# BlinkyBoard_wide.net
KiCad netlist of a schematic drawn in EAGLE
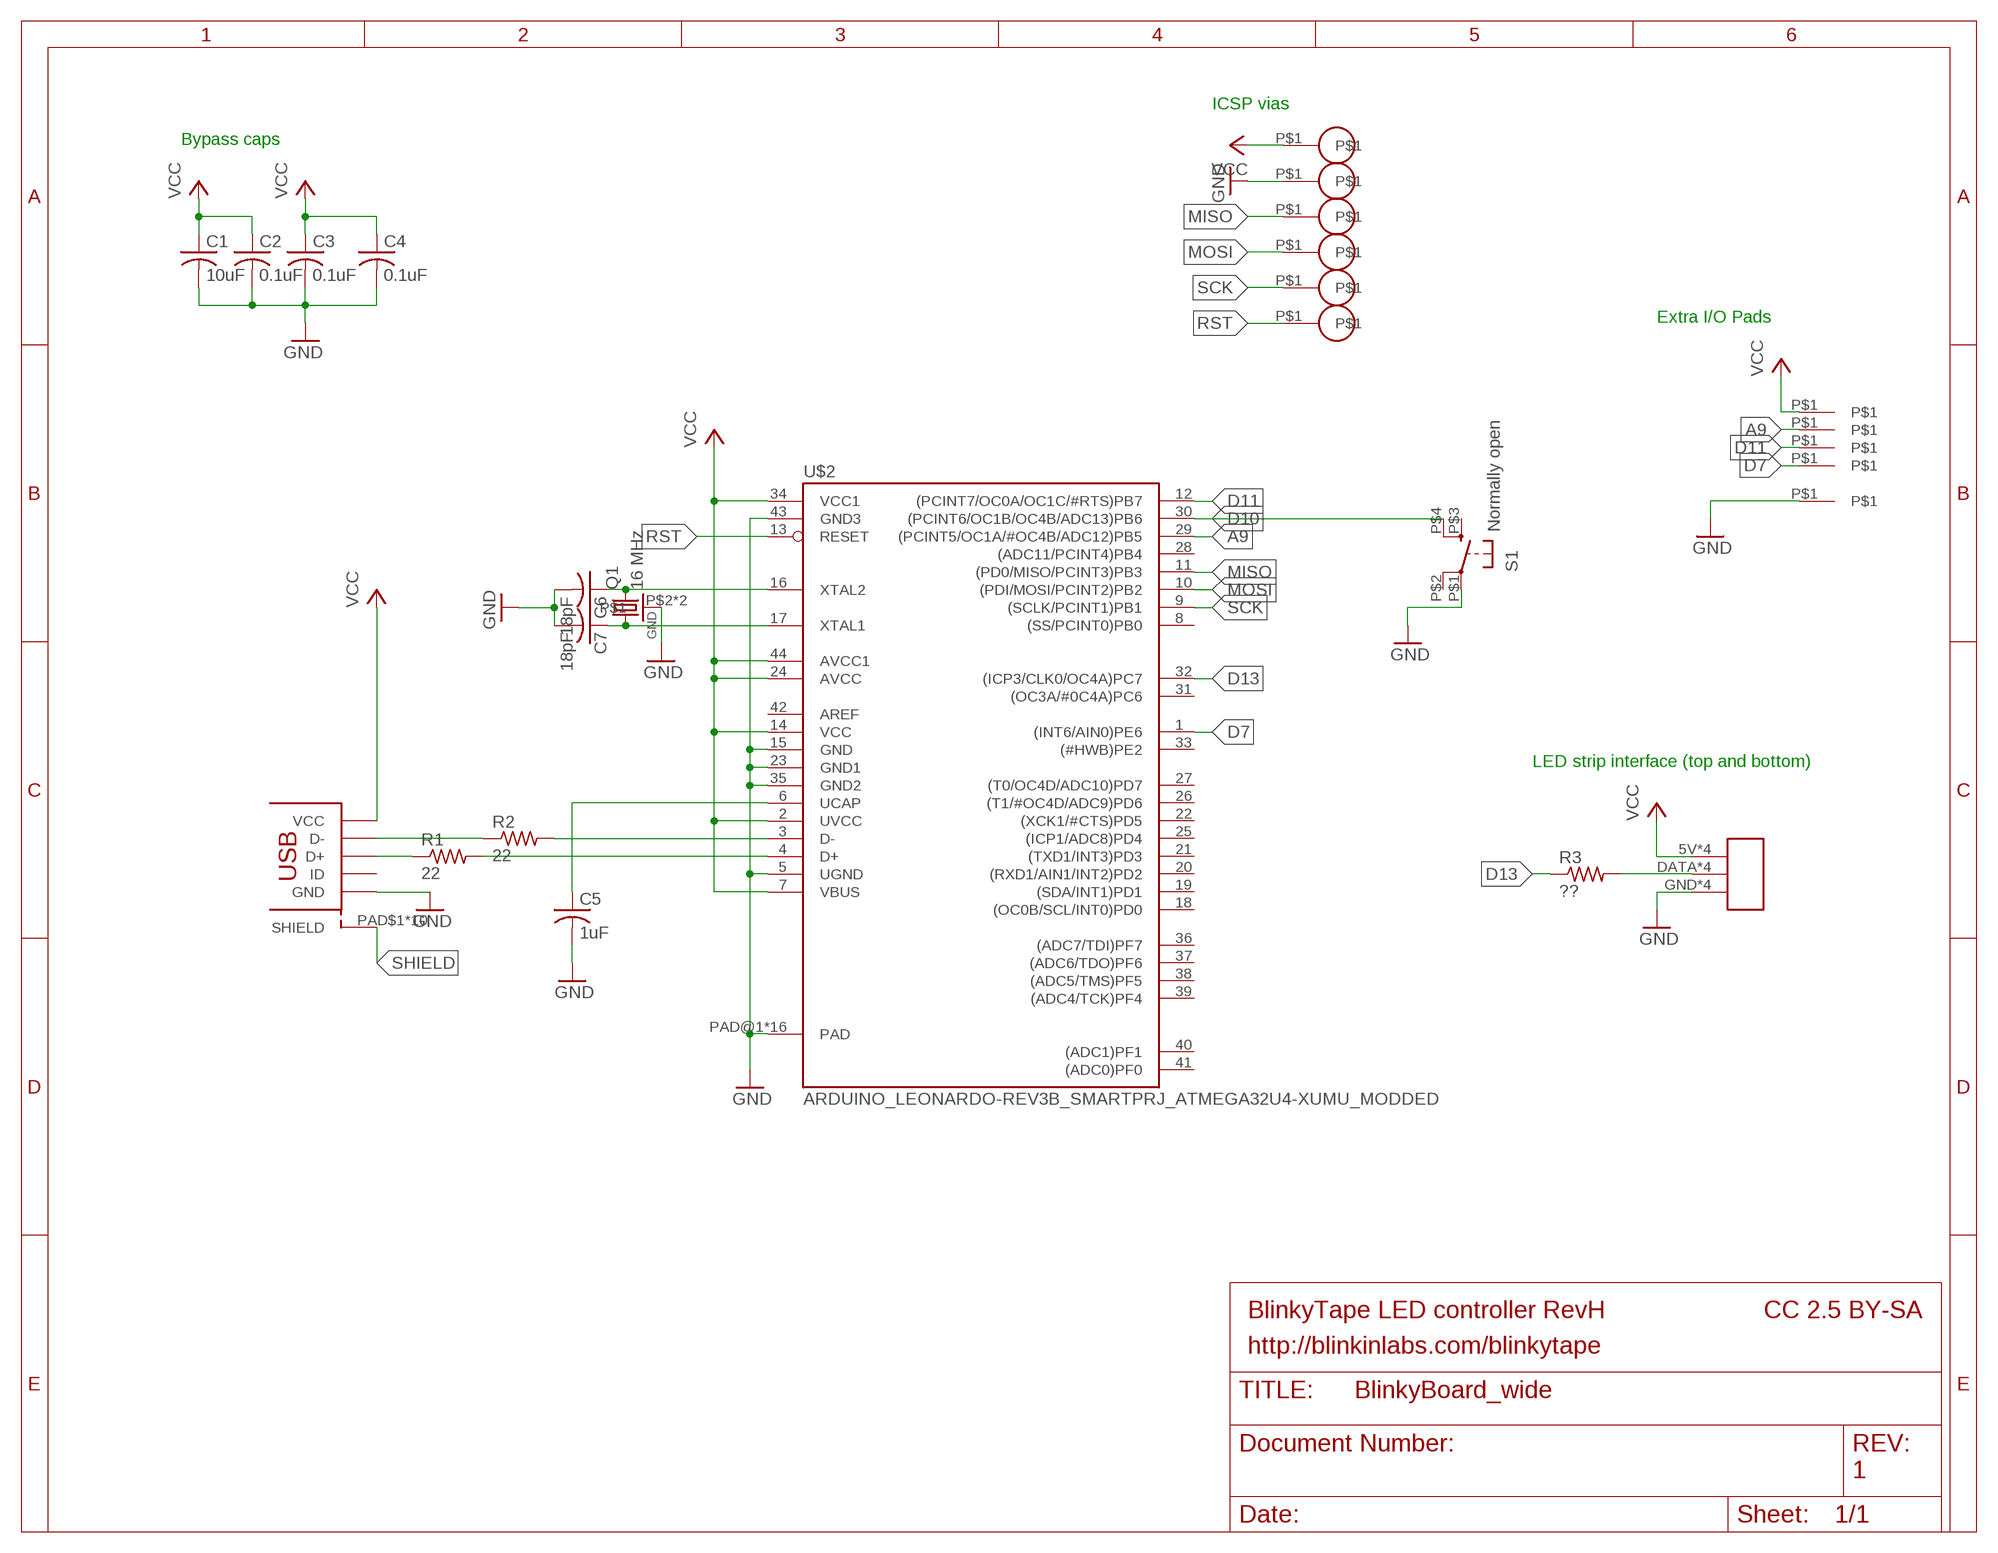
[diagram p0: schematic, sheet 1]

(export (version "E")
  (design (tool "Eeschema 10.0.6"))
  (components
    (comp (ref "C1")
      (value "10uF")
      (footprint "eagle-import:C0603K")
      (libsource (lib "eagle-import") (part "C-USC0603K"))
    )
    (comp (ref "C2")
      (value "0.1uF")
      (footprint "eagle-import:CAP_0402_KEMET_MEDIAN")
      (libsource (lib "eagle-import") (part "C_US"))
    )
    (comp (ref "C3")
      (value "0.1uF")
      (footprint "eagle-import:CAP_0402_KEMET_MEDIAN")
      (libsource (lib "eagle-import") (part "C_US"))
    )
    (comp (ref "C4")
      (value "0.1uF")
      (footprint "eagle-import:CAP_0402_KEMET_MEDIAN")
      (libsource (lib "eagle-import") (part "C_US"))
    )
    (comp (ref "C5")
      (value "1uF")
      (footprint "eagle-import:CAP_0402_KEMET_MEDIAN")
      (libsource (lib "eagle-import") (part "C_US"))
    )
    (comp (ref "C6")
      (value "18pF")
      (footprint "eagle-import:CAP_0402_KEMET_MEDIAN")
      (libsource (lib "eagle-import") (part "C_US"))
    )
    (comp (ref "C7")
      (value "18pF")
      (footprint "eagle-import:CAP_0402_KEMET_MEDIAN")
      (libsource (lib "eagle-import") (part "C_US"))
    )
    (comp (ref "Q1")
      (value "16 MHz")
      (footprint "eagle-import:CRSYTAL_2520")
      (libsource (lib "eagle-import") (part "CRYSTAL_4PAD2520"))
    )
    (comp (ref "R1")
      (value "22")
      (footprint "eagle-import:RES_0402_KEMET_MEDIAN")
      (libsource (lib "eagle-import") (part "R_US"))
    )
    (comp (ref "R2")
      (value "22")
      (footprint "eagle-import:RES_0402_KEMET_MEDIAN")
      (libsource (lib "eagle-import") (part "R_US"))
    )
    (comp (ref "R3")
      (value "??")
      (footprint "eagle-import:RES_0402_KEMET_MEDIAN")
      (libsource (lib "eagle-import") (part "R_US"))
    )
    (comp (ref "S1")
      (value "Normally open")
      (footprint "eagle-import:GLOWBOARD_KMR211G_SWITCH")
      (libsource (lib "eagle-import") (part "GLOWBOARD_KMR211G"))
    )
    (comp (ref "U$1")
      (value "TEST_VIA")
      (footprint "eagle-import:TEST_VIA_.5MM")
      (libsource (lib "eagle-import") (part "TEST_VIA"))
    )
    (comp (ref "U$2")
      (value "ARDUINO_LEONARDO-REV3B_SMARTPRJ_ATMEGA32U4-XUMU_MODDED")
      (footprint "eagle-import:QFN44ML_7X7_LONGLEADS_MOD")
      (libsource (lib "eagle-import") (part "ARDUINO_LEONARDO-REV3B_SMARTPRJ_ATMEGA32U4-XUMU_MODDED"))
    )
    (comp (ref "U$3")
      (value "TEST_VIA")
      (footprint "eagle-import:TEST_VIA_.5MM")
      (libsource (lib "eagle-import") (part "TEST_VIA"))
    )
    (comp (ref "U$4")
      (value "MICRO_USBSMT+THRUHULE")
      (footprint "eagle-import:MICRO_USB_FCI_THRUHOLE")
      (libsource (lib "eagle-import") (part "MICRO_USBSMT+THRUHULE"))
    )
    (comp (ref "U$5")
      (value "TEST_VIA")
      (footprint "eagle-import:TEST_VIA_.5MM")
      (libsource (lib "eagle-import") (part "TEST_VIA"))
    )
    (comp (ref "U$6")
      (value "TEST_VIA")
      (footprint "eagle-import:TEST_VIA_.5MM")
      (libsource (lib "eagle-import") (part "TEST_VIA"))
    )
    (comp (ref "U$7")
      (value "TEST_VIA")
      (footprint "eagle-import:TEST_VIA_.5MM")
      (libsource (lib "eagle-import") (part "TEST_VIA"))
    )
    (comp (ref "U$8")
      (value "TEST_VIA")
      (footprint "eagle-import:TEST_VIA_.5MM")
      (libsource (lib "eagle-import") (part "TEST_VIA"))
    )
    (comp (ref "U$9")
      (value "WS2812B_CONNECTORWIDE")
      (footprint "eagle-import:WS2812B_WIDE_CONNECTOR")
      (libsource (lib "eagle-import") (part "WS2812B_CONNECTORWIDE"))
    )
    (comp (ref "U$10")
      (value "TEST_PAD_SMT")
      (footprint "eagle-import:TEST_PAD_SMT")
      (libsource (lib "eagle-import") (part "TEST_PAD_SMT"))
    )
    (comp (ref "U$11")
      (value "TEST_PAD_SMT")
      (footprint "eagle-import:TEST_PAD_SMT")
      (libsource (lib "eagle-import") (part "TEST_PAD_SMT"))
    )
    (comp (ref "U$12")
      (value "TEST_PAD_SMT")
      (footprint "eagle-import:TEST_PAD_SMT")
      (libsource (lib "eagle-import") (part "TEST_PAD_SMT"))
    )
    (comp (ref "U$13")
      (value "TEST_PAD_SMT")
      (footprint "eagle-import:TEST_PAD_SMT")
      (libsource (lib "eagle-import") (part "TEST_PAD_SMT"))
    )
    (comp (ref "U$14")
      (value "TEST_PAD_SMT")
      (footprint "eagle-import:TEST_PAD_SMT")
      (libsource (lib "eagle-import") (part "TEST_PAD_SMT"))
    )
  )
  (nets
    (net (code "1") (name "/AREF") (class "Default")
      (node (ref "U$2") (pin "42") (pinfunction "AREF_42") (pintype "power_in"))
    )
    (net (code "2") (name "A9") (class "Default")
      (node (ref "U$11") (pin "P$1") (pinfunction "P$1_P$1") (pintype "bidirectional"))
      (node (ref "U$2") (pin "29") (pinfunction "(PCINT5/OC1A/#OC4B/ADC12)PB5_29") (pintype "bidirectional"))
    )
    (net (code "3") (name "D7") (class "Default")
      (node (ref "U$10") (pin "P$1") (pinfunction "P$1_P$1") (pintype "bidirectional"))
      (node (ref "U$2") (pin "1") (pinfunction "(INT6/AIN0)PE6_1") (pintype "bidirectional"))
    )
    (net (code "4") (name "D10") (class "Default")
      (node (ref "S1") (pin "P$4") (pinfunction "S1_P$4") (pintype "passive"))
      (node (ref "U$2") (pin "30") (pinfunction "(PCINT6/OC1B/OC4B/ADC13)PB6_30") (pintype "bidirectional"))
    )
    (net (code "5") (name "D11") (class "Default")
      (node (ref "U$14") (pin "P$1") (pinfunction "P$1_P$1") (pintype "bidirectional"))
      (node (ref "U$2") (pin "12") (pinfunction "(PCINT7/OC0A/OC1C/#RTS)PB7_12") (pintype "bidirectional"))
    )
    (net (code "6") (name "D13") (class "Default")
      (node (ref "R3") (pin "P$1") (pinfunction "1_P$1") (pintype "passive"))
      (node (ref "U$2") (pin "32") (pinfunction "(ICP3/CLK0/OC4A)PC7_32") (pintype "bidirectional"))
    )
    (net (code "7") (name "GND") (class "Default")
      (node (ref "C1") (pin "2") (pinfunction "2_2") (pintype "passive"))
      (node (ref "C2") (pin "P$2") (pinfunction "2_P$2") (pintype "passive"))
      (node (ref "C3") (pin "P$2") (pinfunction "2_P$2") (pintype "passive"))
      (node (ref "C4") (pin "P$2") (pinfunction "2_P$2") (pintype "passive"))
      (node (ref "C5") (pin "P$2") (pinfunction "2_P$2") (pintype "passive"))
      (node (ref "C6") (pin "P$2") (pinfunction "2_P$2") (pintype "passive"))
      (node (ref "C7") (pin "P$2") (pinfunction "2_P$2") (pintype "passive"))
      (node (ref "Q1") (pin "P$2") (pinfunction "P$1_P$2") (pintype "bidirectional"))
      (node (ref "Q1") (pin "P$4") (pinfunction "P$1_P$4") (pintype "bidirectional"))
      (node (ref "S1") (pin "P$1") (pinfunction "P_P$1") (pintype "passive"))
      (node (ref "U$13") (pin "P$1") (pinfunction "P$1_P$1") (pintype "bidirectional"))
      (node (ref "U$2") (pin "15") (pinfunction "GND_15") (pintype "power_in"))
      (node (ref "U$2") (pin "23") (pinfunction "GND1_23") (pintype "power_in"))
      (node (ref "U$2") (pin "35") (pinfunction "GND2_35") (pintype "power_in"))
      (node (ref "U$2") (pin "43") (pinfunction "GND3_43") (pintype "power_in"))
      (node (ref "U$2") (pin "5") (pinfunction "UGND_5") (pintype "power_in"))
      (node (ref "U$2") (pin "PAD@1") (pinfunction "PAD_PAD@1") (pintype "power_in"))
      (node (ref "U$2") (pin "PAD@10") (pinfunction "PAD_PAD@10") (pintype "power_in"))
      (node (ref "U$2") (pin "PAD@11") (pinfunction "PAD_PAD@11") (pintype "power_in"))
      (node (ref "U$2") (pin "PAD@12") (pinfunction "PAD_PAD@12") (pintype "power_in"))
      (node (ref "U$2") (pin "PAD@13") (pinfunction "PAD_PAD@13") (pintype "power_in"))
      (node (ref "U$2") (pin "PAD@14") (pinfunction "PAD_PAD@14") (pintype "power_in"))
      (node (ref "U$2") (pin "PAD@15") (pinfunction "PAD_PAD@15") (pintype "power_in"))
      (node (ref "U$2") (pin "PAD@16") (pinfunction "PAD_PAD@16") (pintype "power_in"))
      (node (ref "U$2") (pin "PAD@2") (pinfunction "PAD_PAD@2") (pintype "power_in"))
      (node (ref "U$2") (pin "PAD@3") (pinfunction "PAD_PAD@3") (pintype "power_in"))
      (node (ref "U$2") (pin "PAD@4") (pinfunction "PAD_PAD@4") (pintype "power_in"))
      (node (ref "U$2") (pin "PAD@5") (pinfunction "PAD_PAD@5") (pintype "power_in"))
      (node (ref "U$2") (pin "PAD@6") (pinfunction "PAD_PAD@6") (pintype "power_in"))
      (node (ref "U$2") (pin "PAD@7") (pinfunction "PAD_PAD@7") (pintype "power_in"))
      (node (ref "U$2") (pin "PAD@8") (pinfunction "PAD_PAD@8") (pintype "power_in"))
      (node (ref "U$2") (pin "PAD@9") (pinfunction "PAD_PAD@9") (pintype "power_in"))
      (node (ref "U$4") (pin "PIN$5") (pinfunction "GND_PIN$5") (pintype "bidirectional"))
      (node (ref "U$7") (pin "P$1") (pinfunction "P$1_P$1") (pintype "bidirectional"))
      (node (ref "U$9") (pin "GND") (pinfunction "GND_GND") (pintype "bidirectional"))
      (node (ref "U$9") (pin "GND1") (pinfunction "GND_GND1") (pintype "bidirectional"))
      (node (ref "U$9") (pin "GND_1") (pinfunction "GND_GND_1") (pintype "bidirectional"))
      (node (ref "U$9") (pin "GND_2") (pinfunction "GND_GND_2") (pintype "bidirectional"))
    )
    (net (code "8") (name "MISO") (class "Default")
      (node (ref "U$1") (pin "P$1") (pinfunction "P$1_P$1") (pintype "bidirectional"))
      (node (ref "U$2") (pin "11") (pinfunction "(PD0/MISO/PCINT3)PB3_11") (pintype "bidirectional"))
    )
    (net (code "9") (name "MOSI") (class "Default")
      (node (ref "U$2") (pin "10") (pinfunction "(PDI/MOSI/PCINT2)PB2_10") (pintype "bidirectional"))
      (node (ref "U$3") (pin "P$1") (pinfunction "P$1_P$1") (pintype "bidirectional"))
    )
    (net (code "10") (name "Net-(C5-1)") (class "Default")
      (node (ref "C5") (pin "P$1") (pinfunction "1_P$1") (pintype "passive"))
      (node (ref "U$2") (pin "6") (pinfunction "UCAP_6") (pintype "passive"))
    )
    (net (code "11") (name "Net-(C6-1)") (class "Default")
      (node (ref "C6") (pin "P$1") (pinfunction "1_P$1") (pintype "passive"))
      (node (ref "Q1") (pin "P$3") (pinfunction "2_P$3") (pintype "passive"))
      (node (ref "U$2") (pin "16") (pinfunction "XTAL2_16") (pintype "bidirectional"))
    )
    (net (code "12") (name "Net-(C7-1)") (class "Default")
      (node (ref "C7") (pin "P$1") (pinfunction "1_P$1") (pintype "passive"))
      (node (ref "Q1") (pin "P$1") (pinfunction "1_P$1") (pintype "passive"))
      (node (ref "U$2") (pin "17") (pinfunction "XTAL1_17") (pintype "bidirectional"))
    )
    (net (code "13") (name "Net-(R1-1)") (class "Default")
      (node (ref "R1") (pin "P$1") (pinfunction "1_P$1") (pintype "passive"))
      (node (ref "U$4") (pin "PIN$3") (pinfunction "D+_PIN$3") (pintype "bidirectional"))
    )
    (net (code "14") (name "Net-(R1-2)") (class "Default")
      (node (ref "R1") (pin "P$2") (pinfunction "2_P$2") (pintype "passive"))
      (node (ref "U$2") (pin "4") (pinfunction "D+_4") (pintype "bidirectional"))
    )
    (net (code "15") (name "Net-(R2-1)") (class "Default")
      (node (ref "R2") (pin "P$1") (pinfunction "1_P$1") (pintype "passive"))
      (node (ref "U$4") (pin "PIN$2") (pinfunction "D-_PIN$2") (pintype "bidirectional"))
    )
    (net (code "16") (name "Net-(R2-2)") (class "Default")
      (node (ref "R2") (pin "P$2") (pinfunction "2_P$2") (pintype "passive"))
      (node (ref "U$2") (pin "3") (pinfunction "D-_3") (pintype "bidirectional"))
    )
    (net (code "17") (name "Net-(R3-2)") (class "Default")
      (node (ref "R3") (pin "P$2") (pinfunction "2_P$2") (pintype "passive"))
      (node (ref "U$9") (pin "DATA") (pinfunction "DATA_DATA") (pintype "bidirectional"))
      (node (ref "U$9") (pin "DATA1") (pinfunction "DATA_DATA1") (pintype "bidirectional"))
      (node (ref "U$9") (pin "DATA_1") (pinfunction "DATA_DATA_1") (pintype "bidirectional"))
      (node (ref "U$9") (pin "DATA_2") (pinfunction "DATA_DATA_2") (pintype "bidirectional"))
    )
    (net (code "18") (name "RST") (class "Default")
      (node (ref "U$2") (pin "13") (pinfunction "RESET_13") (pintype "input"))
      (node (ref "U$6") (pin "P$1") (pinfunction "P$1_P$1") (pintype "bidirectional"))
    )
    (net (code "19") (name "SCK") (class "Default")
      (node (ref "U$2") (pin "9") (pinfunction "(SCLK/PCINT1)PB1_9") (pintype "bidirectional"))
      (node (ref "U$5") (pin "P$1") (pinfunction "P$1_P$1") (pintype "bidirectional"))
    )
    (net (code "20") (name "SHIELD") (class "Default")
      (node (ref "U$4") (pin "PAD$1") (pinfunction "SHIELD_PAD$1") (pintype "bidirectional"))
      (node (ref "U$4") (pin "PAD$10") (pinfunction "SHIELD_PAD$10") (pintype "bidirectional"))
      (node (ref "U$4") (pin "PAD$2") (pinfunction "SHIELD_PAD$2") (pintype "bidirectional"))
      (node (ref "U$4") (pin "PAD$3") (pinfunction "SHIELD_PAD$3") (pintype "bidirectional"))
      (node (ref "U$4") (pin "PAD$4") (pinfunction "SHIELD_PAD$4") (pintype "bidirectional"))
      (node (ref "U$4") (pin "PAD$5") (pinfunction "SHIELD_PAD$5") (pintype "bidirectional"))
      (node (ref "U$4") (pin "PAD$6") (pinfunction "SHIELD_PAD$6") (pintype "bidirectional"))
      (node (ref "U$4") (pin "PAD$7") (pinfunction "SHIELD_PAD$7") (pintype "bidirectional"))
      (node (ref "U$4") (pin "PAD$8") (pinfunction "SHIELD_PAD$8") (pintype "bidirectional"))
      (node (ref "U$4") (pin "PAD$9") (pinfunction "SHIELD_PAD$9") (pintype "bidirectional"))
    )
    (net (code "21") (name "VCC") (class "Default")
      (node (ref "C1") (pin "1") (pinfunction "1_1") (pintype "passive"))
      (node (ref "C2") (pin "P$1") (pinfunction "1_P$1") (pintype "passive"))
      (node (ref "C3") (pin "P$1") (pinfunction "1_P$1") (pintype "passive"))
      (node (ref "C4") (pin "P$1") (pinfunction "1_P$1") (pintype "passive"))
      (node (ref "U$12") (pin "P$1") (pinfunction "P$1_P$1") (pintype "bidirectional"))
      (node (ref "U$2") (pin "14") (pinfunction "VCC_14") (pintype "power_in"))
      (node (ref "U$2") (pin "2") (pinfunction "UVCC_2") (pintype "power_in"))
      (node (ref "U$2") (pin "24") (pinfunction "AVCC_24") (pintype "power_in"))
      (node (ref "U$2") (pin "34") (pinfunction "VCC1_34") (pintype "power_in"))
      (node (ref "U$2") (pin "44") (pinfunction "AVCC1_44") (pintype "power_in"))
      (node (ref "U$2") (pin "7") (pinfunction "VBUS_7") (pintype "input"))
      (node (ref "U$4") (pin "PIN$1") (pinfunction "VCC_PIN$1") (pintype "bidirectional"))
      (node (ref "U$8") (pin "P$1") (pinfunction "P$1_P$1") (pintype "bidirectional"))
      (node (ref "U$9") (pin "5V") (pinfunction "5V_5V") (pintype "bidirectional"))
      (node (ref "U$9") (pin "5V1") (pinfunction "5V_5V1") (pintype "bidirectional"))
      (node (ref "U$9") (pin "5V_1") (pinfunction "5V_5V_1") (pintype "bidirectional"))
      (node (ref "U$9") (pin "5V_2") (pinfunction "5V_5V_2") (pintype "bidirectional"))
    )
    (net (code "22") (name "unconnected-(S1-P1-PadP$2)") (class "Default")
      (node (ref "S1") (pin "P$2") (pinfunction "P1_P$2") (pintype "passive"))
    )
    (net (code "23") (name "unconnected-(S1-S-PadP$3)") (class "Default")
      (node (ref "S1") (pin "P$3") (pinfunction "S_P$3") (pintype "passive"))
    )
    (net (code "24") (name "unconnected-(U$2-(#HWB)PE2-Pad33)") (class "Default")
      (node (ref "U$2") (pin "33") (pinfunction "(#HWB)PE2_33") (pintype "bidirectional"))
    )
    (net (code "25") (name "unconnected-(U$2-(ADC0)PF0-Pad41)") (class "Default")
      (node (ref "U$2") (pin "41") (pinfunction "(ADC0)PF0_41") (pintype "bidirectional"))
    )
    (net (code "26") (name "unconnected-(U$2-(ADC1)PF1-Pad40)") (class "Default")
      (node (ref "U$2") (pin "40") (pinfunction "(ADC1)PF1_40") (pintype "bidirectional"))
    )
    (net (code "27") (name "unconnected-(U$2-(ADC4{slash}TCK)PF4-Pad39)") (class "Default")
      (node (ref "U$2") (pin "39") (pinfunction "(ADC4/TCK)PF4_39") (pintype "bidirectional"))
    )
    (net (code "28") (name "unconnected-(U$2-(ADC5{slash}TMS)PF5-Pad38)") (class "Default")
      (node (ref "U$2") (pin "38") (pinfunction "(ADC5/TMS)PF5_38") (pintype "bidirectional"))
    )
    (net (code "29") (name "unconnected-(U$2-(ADC6{slash}TDO)PF6-Pad37)") (class "Default")
      (node (ref "U$2") (pin "37") (pinfunction "(ADC6/TDO)PF6_37") (pintype "bidirectional"))
    )
    (net (code "30") (name "unconnected-(U$2-(ADC7{slash}TDI)PF7-Pad36)") (class "Default")
      (node (ref "U$2") (pin "36") (pinfunction "(ADC7/TDI)PF7_36") (pintype "bidirectional"))
    )
    (net (code "31") (name "unconnected-(U$2-(ADC11{slash}PCINT4)PB4-Pad28)") (class "Default")
      (node (ref "U$2") (pin "28") (pinfunction "(ADC11/PCINT4)PB4_28") (pintype "bidirectional"))
    )
    (net (code "32") (name "unconnected-(U$2-(ICP1{slash}ADC8)PD4-Pad25)") (class "Default")
      (node (ref "U$2") (pin "25") (pinfunction "(ICP1/ADC8)PD4_25") (pintype "bidirectional"))
    )
    (net (code "33") (name "unconnected-(U$2-(OC0B{slash}SCL{slash}INT0)PD0-Pad18)") (class "Default")
      (node (ref "U$2") (pin "18") (pinfunction "(OC0B/SCL/INT0)PD0_18") (pintype "bidirectional"))
    )
    (net (code "34") (name "unconnected-(U$2-(OC3A{slash}#0C4A)PC6-Pad31)") (class "Default")
      (node (ref "U$2") (pin "31") (pinfunction "(OC3A/#0C4A)PC6_31") (pintype "bidirectional"))
    )
    (net (code "35") (name "unconnected-(U$2-(RXD1{slash}AIN1{slash}INT2)PD2-Pad20)") (class "Default")
      (node (ref "U$2") (pin "20") (pinfunction "(RXD1/AIN1/INT2)PD2_20") (pintype "bidirectional"))
    )
    (net (code "36") (name "unconnected-(U$2-(SDA{slash}INT1)PD1-Pad19)") (class "Default")
      (node (ref "U$2") (pin "19") (pinfunction "(SDA/INT1)PD1_19") (pintype "bidirectional"))
    )
    (net (code "37") (name "unconnected-(U$2-(SS{slash}PCINT0)PB0-Pad8)") (class "Default")
      (node (ref "U$2") (pin "8") (pinfunction "(SS/PCINT0)PB0_8") (pintype "bidirectional"))
    )
    (net (code "38") (name "unconnected-(U$2-(T0{slash}OC4D{slash}ADC10)PD7-Pad27)") (class "Default")
      (node (ref "U$2") (pin "27") (pinfunction "(T0/OC4D/ADC10)PD7_27") (pintype "bidirectional"))
    )
    (net (code "39") (name "unconnected-(U$2-(T1{slash}#OC4D{slash}ADC9)PD6-Pad26)") (class "Default")
      (node (ref "U$2") (pin "26") (pinfunction "(T1/#OC4D/ADC9)PD6_26") (pintype "bidirectional"))
    )
    (net (code "40") (name "unconnected-(U$2-(TXD1{slash}INT3)PD3-Pad21)") (class "Default")
      (node (ref "U$2") (pin "21") (pinfunction "(TXD1/INT3)PD3_21") (pintype "bidirectional"))
    )
    (net (code "41") (name "unconnected-(U$2-(XCK1{slash}#CTS)PD5-Pad22)") (class "Default")
      (node (ref "U$2") (pin "22") (pinfunction "(XCK1/#CTS)PD5_22") (pintype "bidirectional"))
    )
    (net (code "42") (name "unconnected-(U$4-ID-PadPIN$4)") (class "Default")
      (node (ref "U$4") (pin "PIN$4") (pinfunction "ID_PIN$4") (pintype "bidirectional"))
    )
  )
)
